# dimmer.net
KiCad netlist of a schematic drawn in EAGLE
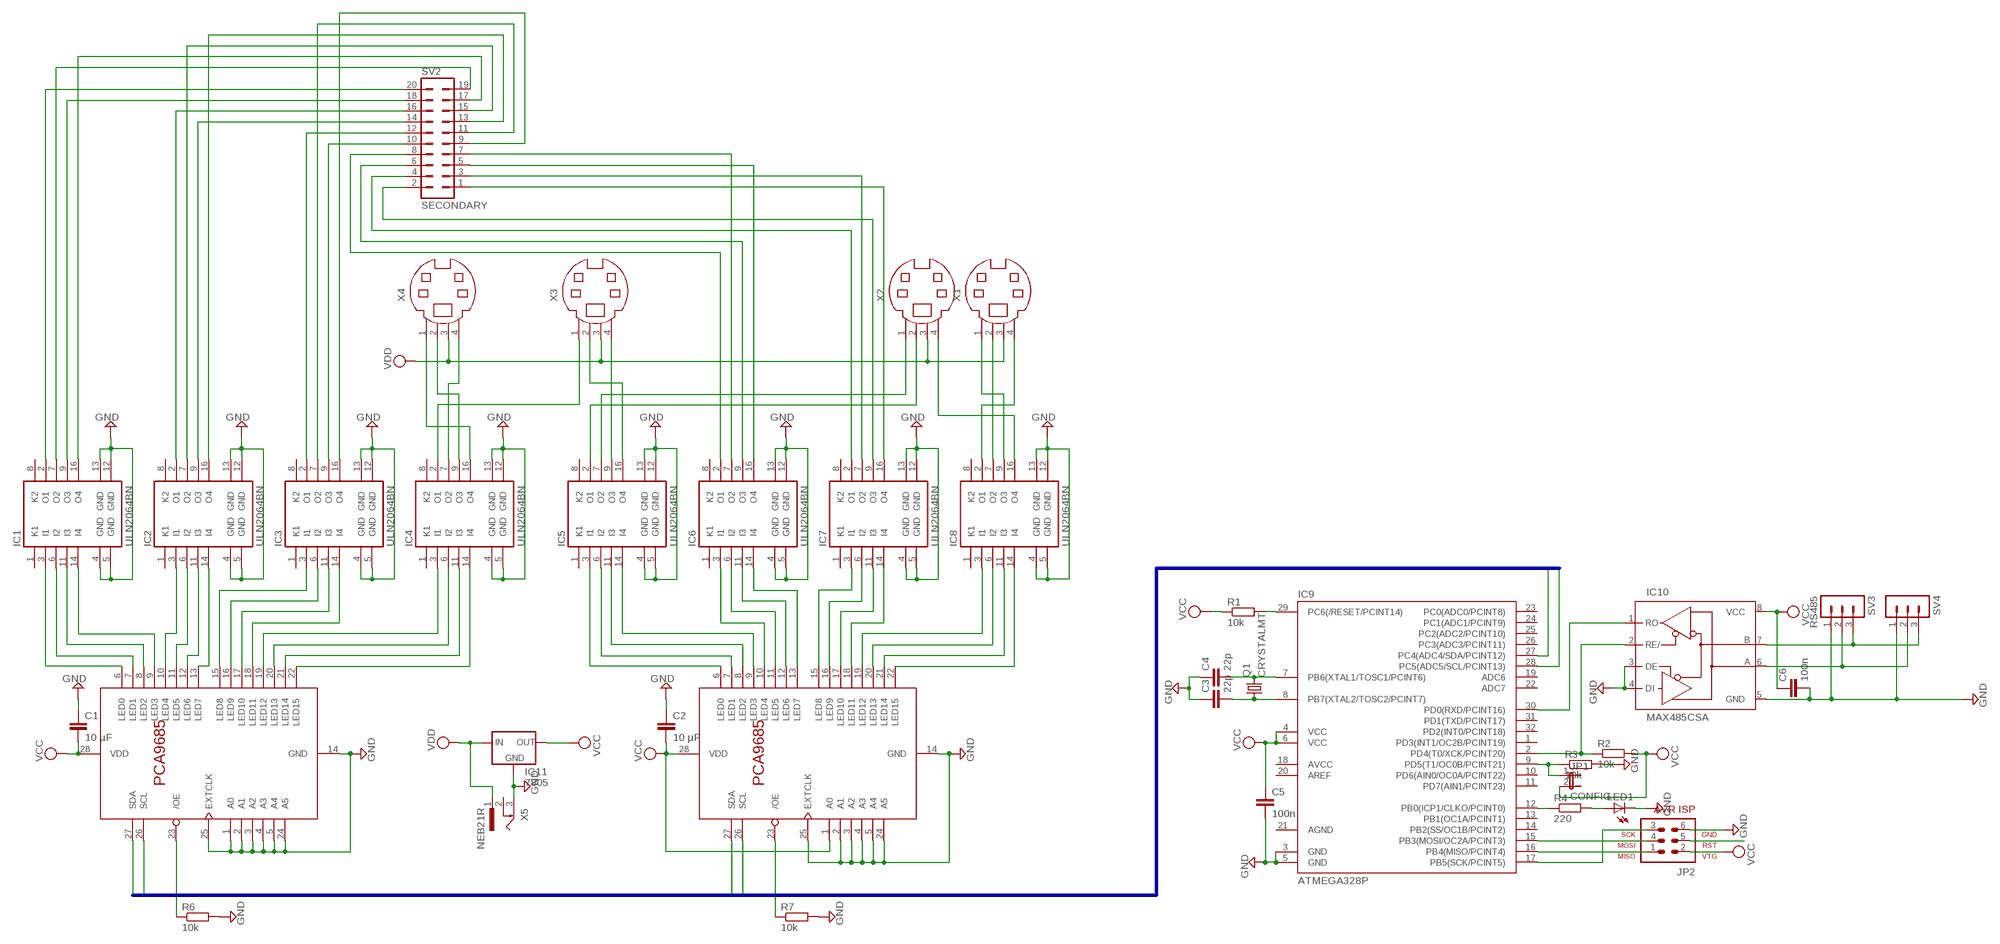
[diagram p0: schematic, sheet 1]

(export (version "E")
  (design (tool "Eeschema 10.0.6"))
  (components
    (comp (ref "C1")
      (value "10 µF")
      (footprint "eagle-import:C0805")
      (libsource (lib "eagle-import") (part "C-EUC0805"))
    )
    (comp (ref "C2")
      (value "10 µF")
      (footprint "eagle-import:C0805")
      (libsource (lib "eagle-import") (part "C-EUC0805"))
    )
    (comp (ref "C3")
      (value "22p")
      (footprint "eagle-import:C0805")
      (libsource (lib "eagle-import") (part "C-EUC0805"))
    )
    (comp (ref "C4")
      (value "22p")
      (footprint "eagle-import:C0805")
      (libsource (lib "eagle-import") (part "C-EUC0805"))
    )
    (comp (ref "C5")
      (value "100n")
      (footprint "eagle-import:C0805")
      (libsource (lib "eagle-import") (part "C-EUC0805"))
    )
    (comp (ref "C6")
      (value "100n")
      (footprint "eagle-import:C0805")
      (libsource (lib "eagle-import") (part "C-EUC0805"))
    )
    (comp (ref "IC1")
      (value "ULN2064BN")
      (footprint "eagle-import:DIL16")
      (libsource (lib "eagle-import") (part "ULN2064BN"))
    )
    (comp (ref "IC2")
      (value "ULN2064BN")
      (footprint "eagle-import:DIL16")
      (libsource (lib "eagle-import") (part "ULN2064BN"))
    )
    (comp (ref "IC3")
      (value "ULN2064BN")
      (footprint "eagle-import:DIL16")
      (libsource (lib "eagle-import") (part "ULN2064BN"))
    )
    (comp (ref "IC4")
      (value "ULN2064BN")
      (footprint "eagle-import:DIL16")
      (libsource (lib "eagle-import") (part "ULN2064BN"))
    )
    (comp (ref "IC5")
      (value "ULN2064BN")
      (footprint "eagle-import:DIL16")
      (libsource (lib "eagle-import") (part "ULN2064BN"))
    )
    (comp (ref "IC6")
      (value "ULN2064BN")
      (footprint "eagle-import:DIL16")
      (libsource (lib "eagle-import") (part "ULN2064BN"))
    )
    (comp (ref "IC7")
      (value "ULN2064BN")
      (footprint "eagle-import:DIL16")
      (libsource (lib "eagle-import") (part "ULN2064BN"))
    )
    (comp (ref "IC8")
      (value "ULN2064BN")
      (footprint "eagle-import:DIL16")
      (libsource (lib "eagle-import") (part "ULN2064BN"))
    )
    (comp (ref "IC9")
      (value "ATMEGA328P")
      (footprint "eagle-import:TQFP32-08")
      (libsource (lib "eagle-import") (part "MEGA48/88/168-AU"))
    )
    (comp (ref "IC10")
      (value "MAX485CSA")
      (footprint "eagle-import:SO08")
      (fields (field (name "MPN") "MAX3468CSA+"))
      (libsource (lib "eagle-import") (part "MAX34SA68C"))
    )
    (comp (ref "IC11")
      (value "7805")
      (footprint "eagle-import:78XXS")
      (libsource (lib "eagle-import") (part "78XXS"))
    )
    (comp (ref "JP1")
      (value "CONFIG")
      (footprint "eagle-import:JP1")
      (libsource (lib "eagle-import") (part "JP1E"))
    )
    (comp (ref "JP2")
      (value "AVR-ISP-6")
      (footprint "eagle-import:AVR-ISP-6")
      (libsource (lib "eagle-import") (part "AVR-ISP-6"))
    )
    (comp (ref "LED1")
      (value "LEDCHIP-LED0603")
      (footprint "eagle-import:CHIP-LED0603")
      (libsource (lib "eagle-import") (part "LEDCHIP-LED0603"))
    )
    (comp (ref "Q1")
      (value "CRYSTALMT")
      (footprint "eagle-import:MT")
      (libsource (lib "eagle-import") (part "CRYSTALMT"))
    )
    (comp (ref "R1")
      (value "10k")
      (footprint "eagle-import:R0805")
      (libsource (lib "eagle-import") (part "R-EU_R0805"))
    )
    (comp (ref "R2")
      (value "10k")
      (footprint "eagle-import:R0805")
      (libsource (lib "eagle-import") (part "R-EU_R0805"))
    )
    (comp (ref "R3")
      (value "10k")
      (footprint "eagle-import:R0805")
      (libsource (lib "eagle-import") (part "R-EU_R0805"))
    )
    (comp (ref "R4")
      (value "220")
      (footprint "eagle-import:R0805")
      (libsource (lib "eagle-import") (part "R-EU_R0805"))
    )
    (comp (ref "R6")
      (value "10k")
      (footprint "eagle-import:R0805")
      (libsource (lib "eagle-import") (part "R-EU_R0805"))
    )
    (comp (ref "R7")
      (value "10k")
      (footprint "eagle-import:R0805")
      (libsource (lib "eagle-import") (part "R-EU_R0805"))
    )
    (comp (ref "SV2")
      (value "SECONDARY")
      (footprint "eagle-import:MA10-2")
      (libsource (lib "eagle-import") (part "MA10-2"))
    )
    (comp (ref "SV3")
      (value "RS485")
      (footprint "eagle-import:MA03-1")
      (libsource (lib "eagle-import") (part "MA03-1"))
    )
    (comp (ref "SV4")
      (value "MA03-1")
      (footprint "eagle-import:MA03-1")
      (libsource (lib "eagle-import") (part "MA03-1"))
    )
    (comp (ref "U$1")
      (value "PCA9685PW")
      (footprint "eagle-import:TSSOP28")
      (libsource (lib "eagle-import") (part "PCA9685PW"))
    )
    (comp (ref "U$2")
      (value "PCA9685PW")
      (footprint "eagle-import:TSSOP28")
      (libsource (lib "eagle-import") (part "PCA9685PW"))
    )
    (comp (ref "X1")
      (value "MD04S")
      (footprint "eagle-import:MDIN04S")
      (libsource (lib "eagle-import") (part "MD04S"))
    )
    (comp (ref "X2")
      (value "MD04S")
      (footprint "eagle-import:MDIN04S")
      (libsource (lib "eagle-import") (part "MD04S"))
    )
    (comp (ref "X3")
      (value "MD04S")
      (footprint "eagle-import:MDIN04S")
      (libsource (lib "eagle-import") (part "MD04S"))
    )
    (comp (ref "X4")
      (value "MD04S")
      (footprint "eagle-import:MDIN04S")
      (libsource (lib "eagle-import") (part "MD04S"))
    )
    (comp (ref "X5")
      (value "NEB21R")
      (footprint "eagle-import:NEB21R")
      (fields (field (name "MPN") "NEB 21 R"))
      (libsource (lib "eagle-import") (part "NEB21R"))
    )
  )
  (nets
    (net (code "1") (name "/AGND") (class "Default")
      (node (ref "IC9") (pin "21") (pinfunction "AGND_21") (pintype "power_in"))
    )
    (net (code "2") (name "/RESET") (class "Default")
      (node (ref "IC9") (pin "29") (pinfunction "PC6(/RESET/PCINT14)_29") (pintype "bidirectional"))
      (node (ref "JP2") (pin "5") (pinfunction "5_5") (pintype "passive"))
      (node (ref "R1") (pin "2") (pinfunction "2_2") (pintype "passive"))
    )
    (net (code "3") (name "/SCL") (class "Default")
      (node (ref "IC9") (pin "28") (pinfunction "PC5(ADC5/SCL/PCINT13)_28") (pintype "bidirectional"))
      (node (ref "U$1") (pin "26") (pinfunction "SCL_26") (pintype "bidirectional"))
      (node (ref "U$2") (pin "26") (pinfunction "SCL_26") (pintype "bidirectional"))
    )
    (net (code "4") (name "/SDA") (class "Default")
      (node (ref "IC9") (pin "27") (pinfunction "PC4(ADC4/SDA/PCINT12)_27") (pintype "bidirectional"))
      (node (ref "U$1") (pin "27") (pinfunction "SDA_27") (pintype "bidirectional"))
      (node (ref "U$2") (pin "27") (pinfunction "SDA_27") (pintype "bidirectional"))
    )
    (net (code "5") (name "GND") (class "Default")
      (node (ref "C1") (pin "1") (pinfunction "1_1") (pintype "passive"))
      (node (ref "C2") (pin "1") (pinfunction "1_1") (pintype "passive"))
      (node (ref "C3") (pin "1") (pinfunction "1_1") (pintype "passive"))
      (node (ref "C4") (pin "1") (pinfunction "1_1") (pintype "passive"))
      (node (ref "C5") (pin "2") (pinfunction "2_2") (pintype "passive"))
      (node (ref "C6") (pin "2") (pinfunction "2_2") (pintype "passive"))
      (node (ref "IC1") (pin "12") (pinfunction "GND_12") (pintype "power_in"))
      (node (ref "IC1") (pin "13") (pinfunction "GND_13") (pintype "power_in"))
      (node (ref "IC1") (pin "4") (pinfunction "GND_4") (pintype "power_in"))
      (node (ref "IC1") (pin "5") (pinfunction "GND_5") (pintype "power_in"))
      (node (ref "IC10") (pin "3") (pinfunction "DE_3") (pintype "input"))
      (node (ref "IC10") (pin "4") (pinfunction "DI_4") (pintype "input"))
      (node (ref "IC10") (pin "5") (pinfunction "GND_5") (pintype "power_in"))
      (node (ref "IC11") (pin "GND") (pinfunction "GND_GND") (pintype "input"))
      (node (ref "IC2") (pin "12") (pinfunction "GND_12") (pintype "power_in"))
      (node (ref "IC2") (pin "13") (pinfunction "GND_13") (pintype "power_in"))
      (node (ref "IC2") (pin "4") (pinfunction "GND_4") (pintype "power_in"))
      (node (ref "IC2") (pin "5") (pinfunction "GND_5") (pintype "power_in"))
      (node (ref "IC3") (pin "12") (pinfunction "GND_12") (pintype "power_in"))
      (node (ref "IC3") (pin "13") (pinfunction "GND_13") (pintype "power_in"))
      (node (ref "IC3") (pin "4") (pinfunction "GND_4") (pintype "power_in"))
      (node (ref "IC3") (pin "5") (pinfunction "GND_5") (pintype "power_in"))
      (node (ref "IC4") (pin "12") (pinfunction "GND_12") (pintype "power_in"))
      (node (ref "IC4") (pin "13") (pinfunction "GND_13") (pintype "power_in"))
      (node (ref "IC4") (pin "4") (pinfunction "GND_4") (pintype "power_in"))
      (node (ref "IC4") (pin "5") (pinfunction "GND_5") (pintype "power_in"))
      (node (ref "IC5") (pin "12") (pinfunction "GND_12") (pintype "power_in"))
      (node (ref "IC5") (pin "13") (pinfunction "GND_13") (pintype "power_in"))
      (node (ref "IC5") (pin "4") (pinfunction "GND_4") (pintype "power_in"))
      (node (ref "IC5") (pin "5") (pinfunction "GND_5") (pintype "power_in"))
      (node (ref "IC6") (pin "12") (pinfunction "GND_12") (pintype "power_in"))
      (node (ref "IC6") (pin "13") (pinfunction "GND_13") (pintype "power_in"))
      (node (ref "IC6") (pin "4") (pinfunction "GND_4") (pintype "power_in"))
      (node (ref "IC6") (pin "5") (pinfunction "GND_5") (pintype "power_in"))
      (node (ref "IC7") (pin "12") (pinfunction "GND_12") (pintype "power_in"))
      (node (ref "IC7") (pin "13") (pinfunction "GND_13") (pintype "power_in"))
      (node (ref "IC7") (pin "4") (pinfunction "GND_4") (pintype "power_in"))
      (node (ref "IC7") (pin "5") (pinfunction "GND_5") (pintype "power_in"))
      (node (ref "IC8") (pin "12") (pinfunction "GND_12") (pintype "power_in"))
      (node (ref "IC8") (pin "13") (pinfunction "GND_13") (pintype "power_in"))
      (node (ref "IC8") (pin "4") (pinfunction "GND_4") (pintype "power_in"))
      (node (ref "IC8") (pin "5") (pinfunction "GND_5") (pintype "power_in"))
      (node (ref "IC9") (pin "3") (pinfunction "GND_3") (pintype "power_in"))
      (node (ref "IC9") (pin "5") (pinfunction "GND_5") (pintype "power_in"))
      (node (ref "JP2") (pin "6") (pinfunction "6_6") (pintype "passive"))
      (node (ref "LED1") (pin "C") (pinfunction "C_C") (pintype "passive"))
      (node (ref "R3") (pin "2") (pinfunction "2_2") (pintype "passive"))
      (node (ref "R6") (pin "2") (pinfunction "2_2") (pintype "passive"))
      (node (ref "R7") (pin "2") (pinfunction "2_2") (pintype "passive"))
      (node (ref "SV3") (pin "1") (pinfunction "1_1") (pintype "passive"))
      (node (ref "SV4") (pin "1") (pinfunction "1_1") (pintype "passive"))
      (node (ref "U$1") (pin "1") (pinfunction "A0_1") (pintype "bidirectional"))
      (node (ref "U$1") (pin "14") (pinfunction "GND_14") (pintype "power_in"))
      (node (ref "U$1") (pin "2") (pinfunction "A1_2") (pintype "bidirectional"))
      (node (ref "U$1") (pin "24") (pinfunction "A5_24") (pintype "bidirectional"))
      (node (ref "U$1") (pin "25") (pinfunction "EXTCLK_25") (pintype "input"))
      (node (ref "U$1") (pin "3") (pinfunction "A2_3") (pintype "bidirectional"))
      (node (ref "U$1") (pin "4") (pinfunction "A3_4") (pintype "bidirectional"))
      (node (ref "U$1") (pin "5") (pinfunction "A4_5") (pintype "bidirectional"))
      (node (ref "U$2") (pin "14") (pinfunction "GND_14") (pintype "power_in"))
      (node (ref "U$2") (pin "2") (pinfunction "A1_2") (pintype "bidirectional"))
      (node (ref "U$2") (pin "24") (pinfunction "A5_24") (pintype "bidirectional"))
      (node (ref "U$2") (pin "25") (pinfunction "EXTCLK_25") (pintype "input"))
      (node (ref "U$2") (pin "3") (pinfunction "A2_3") (pintype "bidirectional"))
      (node (ref "U$2") (pin "4") (pinfunction "A3_4") (pintype "bidirectional"))
      (node (ref "U$2") (pin "5") (pinfunction "A4_5") (pintype "bidirectional"))
      (node (ref "X5") (pin "3") (pinfunction "3_3") (pintype "passive"))
    )
    (net (code "6") (name "Net-(IC1-I1)") (class "Default")
      (node (ref "IC1") (pin "3") (pinfunction "I1_3") (pintype "input"))
      (node (ref "U$1") (pin "6") (pinfunction "LED0_6") (pintype "bidirectional"))
    )
    (net (code "7") (name "Net-(IC1-I2)") (class "Default")
      (node (ref "IC1") (pin "6") (pinfunction "I2_6") (pintype "input"))
      (node (ref "U$1") (pin "7") (pinfunction "LED1_7") (pintype "bidirectional"))
    )
    (net (code "8") (name "Net-(IC1-I3)") (class "Default")
      (node (ref "IC1") (pin "11") (pinfunction "I3_11") (pintype "input"))
      (node (ref "U$1") (pin "8") (pinfunction "LED2_8") (pintype "bidirectional"))
    )
    (net (code "9") (name "Net-(IC1-I4)") (class "Default")
      (node (ref "IC1") (pin "14") (pinfunction "I4_14") (pintype "input"))
      (node (ref "U$1") (pin "9") (pinfunction "LED3_9") (pintype "bidirectional"))
    )
    (net (code "10") (name "Net-(IC1-O1)") (class "Default")
      (node (ref "IC1") (pin "2") (pinfunction "O1_2") (pintype "open_collector"))
      (node (ref "SV2") (pin "20") (pinfunction "20_20") (pintype "passive"))
    )
    (net (code "11") (name "Net-(IC1-O2)") (class "Default")
      (node (ref "IC1") (pin "7") (pinfunction "O2_7") (pintype "open_collector"))
      (node (ref "SV2") (pin "19") (pinfunction "19_19") (pintype "passive"))
    )
    (net (code "12") (name "Net-(IC1-O3)") (class "Default")
      (node (ref "IC1") (pin "9") (pinfunction "O3_9") (pintype "open_collector"))
      (node (ref "SV2") (pin "18") (pinfunction "18_18") (pintype "passive"))
    )
    (net (code "13") (name "Net-(IC1-O4)") (class "Default")
      (node (ref "IC1") (pin "16") (pinfunction "O4_16") (pintype "open_collector"))
      (node (ref "SV2") (pin "17") (pinfunction "17_17") (pintype "passive"))
    )
    (net (code "14") (name "Net-(IC2-I1)") (class "Default")
      (node (ref "IC2") (pin "3") (pinfunction "I1_3") (pintype "input"))
      (node (ref "U$1") (pin "10") (pinfunction "LED4_10") (pintype "bidirectional"))
    )
    (net (code "15") (name "Net-(IC2-I2)") (class "Default")
      (node (ref "IC2") (pin "6") (pinfunction "I2_6") (pintype "input"))
      (node (ref "U$1") (pin "11") (pinfunction "LED5_11") (pintype "bidirectional"))
    )
    (net (code "16") (name "Net-(IC2-I3)") (class "Default")
      (node (ref "IC2") (pin "11") (pinfunction "I3_11") (pintype "input"))
      (node (ref "U$1") (pin "12") (pinfunction "LED6_12") (pintype "bidirectional"))
    )
    (net (code "17") (name "Net-(IC2-I4)") (class "Default")
      (node (ref "IC2") (pin "14") (pinfunction "I4_14") (pintype "input"))
      (node (ref "U$1") (pin "13") (pinfunction "LED7_13") (pintype "bidirectional"))
    )
    (net (code "18") (name "Net-(IC2-O1)") (class "Default")
      (node (ref "IC2") (pin "2") (pinfunction "O1_2") (pintype "open_collector"))
      (node (ref "SV2") (pin "16") (pinfunction "16_16") (pintype "passive"))
    )
    (net (code "19") (name "Net-(IC2-O2)") (class "Default")
      (node (ref "IC2") (pin "7") (pinfunction "O2_7") (pintype "open_collector"))
      (node (ref "SV2") (pin "15") (pinfunction "15_15") (pintype "passive"))
    )
    (net (code "20") (name "Net-(IC2-O3)") (class "Default")
      (node (ref "IC2") (pin "9") (pinfunction "O3_9") (pintype "open_collector"))
      (node (ref "SV2") (pin "14") (pinfunction "14_14") (pintype "passive"))
    )
    (net (code "21") (name "Net-(IC2-O4)") (class "Default")
      (node (ref "IC2") (pin "16") (pinfunction "O4_16") (pintype "open_collector"))
      (node (ref "SV2") (pin "13") (pinfunction "13_13") (pintype "passive"))
    )
    (net (code "22") (name "Net-(IC3-I1)") (class "Default")
      (node (ref "IC3") (pin "3") (pinfunction "I1_3") (pintype "input"))
      (node (ref "U$1") (pin "15") (pinfunction "LED8_15") (pintype "bidirectional"))
    )
    (net (code "23") (name "Net-(IC3-I2)") (class "Default")
      (node (ref "IC3") (pin "6") (pinfunction "I2_6") (pintype "input"))
      (node (ref "U$1") (pin "16") (pinfunction "LED9_16") (pintype "bidirectional"))
    )
    (net (code "24") (name "Net-(IC3-I3)") (class "Default")
      (node (ref "IC3") (pin "11") (pinfunction "I3_11") (pintype "input"))
      (node (ref "U$1") (pin "17") (pinfunction "LED10_17") (pintype "bidirectional"))
    )
    (net (code "25") (name "Net-(IC3-I4)") (class "Default")
      (node (ref "IC3") (pin "14") (pinfunction "I4_14") (pintype "input"))
      (node (ref "U$1") (pin "18") (pinfunction "LED11_18") (pintype "bidirectional"))
    )
    (net (code "26") (name "Net-(IC3-O1)") (class "Default")
      (node (ref "IC3") (pin "2") (pinfunction "O1_2") (pintype "open_collector"))
      (node (ref "SV2") (pin "12") (pinfunction "12_12") (pintype "passive"))
    )
    (net (code "27") (name "Net-(IC3-O2)") (class "Default")
      (node (ref "IC3") (pin "7") (pinfunction "O2_7") (pintype "open_collector"))
      (node (ref "SV2") (pin "11") (pinfunction "11_11") (pintype "passive"))
    )
    (net (code "28") (name "Net-(IC3-O3)") (class "Default")
      (node (ref "IC3") (pin "9") (pinfunction "O3_9") (pintype "open_collector"))
      (node (ref "SV2") (pin "10") (pinfunction "10_10") (pintype "passive"))
    )
    (net (code "29") (name "Net-(IC3-O4)") (class "Default")
      (node (ref "IC3") (pin "16") (pinfunction "O4_16") (pintype "open_collector"))
      (node (ref "SV2") (pin "9") (pinfunction "9_9") (pintype "passive"))
    )
    (net (code "30") (name "Net-(IC4-I1)") (class "Default")
      (node (ref "IC4") (pin "3") (pinfunction "I1_3") (pintype "input"))
      (node (ref "U$1") (pin "19") (pinfunction "LED12_19") (pintype "bidirectional"))
    )
    (net (code "31") (name "Net-(IC4-I2)") (class "Default")
      (node (ref "IC4") (pin "6") (pinfunction "I2_6") (pintype "input"))
      (node (ref "U$1") (pin "20") (pinfunction "LED13_20") (pintype "bidirectional"))
    )
    (net (code "32") (name "Net-(IC4-I3)") (class "Default")
      (node (ref "IC4") (pin "11") (pinfunction "I3_11") (pintype "input"))
      (node (ref "U$1") (pin "21") (pinfunction "LED14_21") (pintype "bidirectional"))
    )
    (net (code "33") (name "Net-(IC4-I4)") (class "Default")
      (node (ref "IC4") (pin "14") (pinfunction "I4_14") (pintype "input"))
      (node (ref "U$1") (pin "22") (pinfunction "LED15_22") (pintype "bidirectional"))
    )
    (net (code "34") (name "Net-(IC4-O1)") (class "Default")
      (node (ref "IC4") (pin "2") (pinfunction "O1_2") (pintype "open_collector"))
      (node (ref "X3") (pin "1") (pinfunction "1_1") (pintype "passive"))
    )
    (net (code "35") (name "Net-(IC4-O2)") (class "Default")
      (node (ref "IC4") (pin "7") (pinfunction "O2_7") (pintype "open_collector"))
      (node (ref "X4") (pin "4") (pinfunction "4_4") (pintype "passive"))
    )
    (net (code "36") (name "Net-(IC4-O3)") (class "Default")
      (node (ref "IC4") (pin "9") (pinfunction "O3_9") (pintype "open_collector"))
      (node (ref "X4") (pin "2") (pinfunction "2_2") (pintype "passive"))
    )
    (net (code "37") (name "Net-(IC4-O4)") (class "Default")
      (node (ref "IC4") (pin "16") (pinfunction "O4_16") (pintype "open_collector"))
      (node (ref "X4") (pin "1") (pinfunction "1_1") (pintype "passive"))
    )
    (net (code "38") (name "Net-(IC5-I1)") (class "Default")
      (node (ref "IC5") (pin "3") (pinfunction "I1_3") (pintype "input"))
      (node (ref "U$2") (pin "6") (pinfunction "LED0_6") (pintype "bidirectional"))
    )
    (net (code "39") (name "Net-(IC5-I2)") (class "Default")
      (node (ref "IC5") (pin "6") (pinfunction "I2_6") (pintype "input"))
      (node (ref "U$2") (pin "7") (pinfunction "LED1_7") (pintype "bidirectional"))
    )
    (net (code "40") (name "Net-(IC5-I3)") (class "Default")
      (node (ref "IC5") (pin "11") (pinfunction "I3_11") (pintype "input"))
      (node (ref "U$2") (pin "8") (pinfunction "LED2_8") (pintype "bidirectional"))
    )
    (net (code "41") (name "Net-(IC5-I4)") (class "Default")
      (node (ref "IC5") (pin "14") (pinfunction "I4_14") (pintype "input"))
      (node (ref "U$2") (pin "9") (pinfunction "LED3_9") (pintype "bidirectional"))
    )
    (net (code "42") (name "Net-(IC5-O1)") (class "Default")
      (node (ref "IC5") (pin "2") (pinfunction "O1_2") (pintype "open_collector"))
      (node (ref "X2") (pin "2") (pinfunction "2_2") (pintype "passive"))
    )
    (net (code "43") (name "Net-(IC5-O2)") (class "Default")
      (node (ref "IC5") (pin "7") (pinfunction "O2_7") (pintype "open_collector"))
      (node (ref "X2") (pin "1") (pinfunction "1_1") (pintype "passive"))
    )
    (net (code "44") (name "Net-(IC5-O3)") (class "Default")
      (node (ref "IC5") (pin "9") (pinfunction "O3_9") (pintype "open_collector"))
      (node (ref "X3") (pin "4") (pinfunction "4_4") (pintype "passive"))
    )
    (net (code "45") (name "Net-(IC5-O4)") (class "Default")
      (node (ref "IC5") (pin "16") (pinfunction "O4_16") (pintype "open_collector"))
      (node (ref "X3") (pin "2") (pinfunction "2_2") (pintype "passive"))
    )
    (net (code "46") (name "Net-(IC6-I1)") (class "Default")
      (node (ref "IC6") (pin "3") (pinfunction "I1_3") (pintype "input"))
      (node (ref "U$2") (pin "10") (pinfunction "LED4_10") (pintype "bidirectional"))
    )
    (net (code "47") (name "Net-(IC6-I2)") (class "Default")
      (node (ref "IC6") (pin "6") (pinfunction "I2_6") (pintype "input"))
      (node (ref "U$2") (pin "11") (pinfunction "LED5_11") (pintype "bidirectional"))
    )
    (net (code "48") (name "Net-(IC6-I3)") (class "Default")
      (node (ref "IC6") (pin "11") (pinfunction "I3_11") (pintype "input"))
      (node (ref "U$2") (pin "12") (pinfunction "LED6_12") (pintype "bidirectional"))
    )
    (net (code "49") (name "Net-(IC6-I4)") (class "Default")
      (node (ref "IC6") (pin "14") (pinfunction "I4_14") (pintype "input"))
      (node (ref "U$2") (pin "13") (pinfunction "LED7_13") (pintype "bidirectional"))
    )
    (net (code "50") (name "Net-(IC6-O1)") (class "Default")
      (node (ref "IC6") (pin "2") (pinfunction "O1_2") (pintype "open_collector"))
      (node (ref "SV2") (pin "8") (pinfunction "8_8") (pintype "passive"))
    )
    (net (code "51") (name "Net-(IC6-O2)") (class "Default")
      (node (ref "IC6") (pin "7") (pinfunction "O2_7") (pintype "open_collector"))
      (node (ref "SV2") (pin "7") (pinfunction "7_7") (pintype "passive"))
    )
    (net (code "52") (name "Net-(IC6-O3)") (class "Default")
      (node (ref "IC6") (pin "9") (pinfunction "O3_9") (pintype "open_collector"))
      (node (ref "SV2") (pin "6") (pinfunction "6_6") (pintype "passive"))
    )
    (net (code "53") (name "Net-(IC6-O4)") (class "Default")
      (node (ref "IC6") (pin "16") (pinfunction "O4_16") (pintype "open_collector"))
      (node (ref "SV2") (pin "5") (pinfunction "5_5") (pintype "passive"))
    )
    (net (code "54") (name "Net-(IC7-I1)") (class "Default")
      (node (ref "IC7") (pin "3") (pinfunction "I1_3") (pintype "input"))
      (node (ref "U$2") (pin "15") (pinfunction "LED8_15") (pintype "bidirectional"))
    )
    (net (code "55") (name "Net-(IC7-I2)") (class "Default")
      (node (ref "IC7") (pin "6") (pinfunction "I2_6") (pintype "input"))
      (node (ref "U$2") (pin "16") (pinfunction "LED9_16") (pintype "bidirectional"))
    )
    (net (code "56") (name "Net-(IC7-I3)") (class "Default")
      (node (ref "IC7") (pin "11") (pinfunction "I3_11") (pintype "input"))
      (node (ref "U$2") (pin "17") (pinfunction "LED10_17") (pintype "bidirectional"))
    )
    (net (code "57") (name "Net-(IC7-I4)") (class "Default")
      (node (ref "IC7") (pin "14") (pinfunction "I4_14") (pintype "input"))
      (node (ref "U$2") (pin "18") (pinfunction "LED11_18") (pintype "bidirectional"))
    )
    (net (code "58") (name "Net-(IC7-O1)") (class "Default")
      (node (ref "IC7") (pin "2") (pinfunction "O1_2") (pintype "open_collector"))
      (node (ref "SV2") (pin "4") (pinfunction "4_4") (pintype "passive"))
    )
    (net (code "59") (name "Net-(IC7-O2)") (class "Default")
      (node (ref "IC7") (pin "7") (pinfunction "O2_7") (pintype "open_collector"))
      (node (ref "SV2") (pin "3") (pinfunction "3_3") (pintype "passive"))
    )
    (net (code "60") (name "Net-(IC7-O3)") (class "Default")
      (node (ref "IC7") (pin "9") (pinfunction "O3_9") (pintype "open_collector"))
      (node (ref "SV2") (pin "2") (pinfunction "2_2") (pintype "passive"))
    )
    (net (code "61") (name "Net-(IC7-O4)") (class "Default")
      (node (ref "IC7") (pin "16") (pinfunction "O4_16") (pintype "open_collector"))
      (node (ref "SV2") (pin "1") (pinfunction "1_1") (pintype "passive"))
    )
    (net (code "62") (name "Net-(IC8-I1)") (class "Default")
      (node (ref "IC8") (pin "3") (pinfunction "I1_3") (pintype "input"))
      (node (ref "U$2") (pin "19") (pinfunction "LED12_19") (pintype "bidirectional"))
    )
    (net (code "63") (name "Net-(IC8-I2)") (class "Default")
      (node (ref "IC8") (pin "6") (pinfunction "I2_6") (pintype "input"))
      (node (ref "U$2") (pin "20") (pinfunction "LED13_20") (pintype "bidirectional"))
    )
    (net (code "64") (name "Net-(IC8-I3)") (class "Default")
      (node (ref "IC8") (pin "11") (pinfunction "I3_11") (pintype "input"))
      (node (ref "U$2") (pin "21") (pinfunction "LED14_21") (pintype "bidirectional"))
    )
    (net (code "65") (name "Net-(IC8-I4)") (class "Default")
      (node (ref "IC8") (pin "14") (pinfunction "I4_14") (pintype "input"))
      (node (ref "U$2") (pin "22") (pinfunction "LED15_22") (pintype "bidirectional"))
    )
    (net (code "66") (name "Net-(IC8-O1)") (class "Default")
      (node (ref "IC8") (pin "2") (pinfunction "O1_2") (pintype "open_collector"))
      (node (ref "X1") (pin "4") (pinfunction "4_4") (pintype "passive"))
    )
    (net (code "67") (name "Net-(IC8-O2)") (class "Default")
      (node (ref "IC8") (pin "7") (pinfunction "O2_7") (pintype "open_collector"))
      (node (ref "X1") (pin "2") (pinfunction "2_2") (pintype "passive"))
    )
    (net (code "68") (name "Net-(IC8-O3)") (class "Default")
      (node (ref "IC8") (pin "9") (pinfunction "O3_9") (pintype "open_collector"))
      (node (ref "X1") (pin "1") (pinfunction "1_1") (pintype "passive"))
    )
    (net (code "69") (name "Net-(IC8-O4)") (class "Default")
      (node (ref "IC8") (pin "16") (pinfunction "O4_16") (pintype "open_collector"))
      (node (ref "X2") (pin "4") (pinfunction "4_4") (pintype "passive"))
    )
    (net (code "70") (name "Net-(IC9-PB0(ICP1{slash}CLKO{slash}PCINT0))") (class "Default")
      (node (ref "IC9") (pin "12") (pinfunction "PB0(ICP1/CLKO/PCINT0)_12") (pintype "bidirectional"))
      (node (ref "R4") (pin "1") (pinfunction "1_1") (pintype "passive"))
    )
    (net (code "71") (name "Net-(IC9-PB3(MOSI{slash}OC2A{slash}PCINT3))") (class "Default")
      (node (ref "IC9") (pin "15") (pinfunction "PB3(MOSI/OC2A/PCINT3)_15") (pintype "bidirectional"))
      (node (ref "JP2") (pin "4") (pinfunction "4_4") (pintype "passive"))
    )
    (net (code "72") (name "Net-(IC9-PB4(MISO{slash}PCINT4))") (class "Default")
      (node (ref "IC9") (pin "16") (pinfunction "PB4(MISO/PCINT4)_16") (pintype "bidirectional"))
      (node (ref "JP2") (pin "1") (pinfunction "1_1") (pintype "passive"))
    )
    (net (code "73") (name "Net-(IC9-PB5(SCK{slash}PCINT5))") (class "Default")
      (node (ref "IC9") (pin "17") (pinfunction "PB5(SCK/PCINT5)_17") (pintype "bidirectional"))
      (node (ref "JP2") (pin "3") (pinfunction "3_3") (pintype "passive"))
    )
    (net (code "74") (name "Net-(IC9-PB6(XTAL1{slash}TOSC1{slash}PCINT6))") (class "Default")
      (node (ref "C4") (pin "2") (pinfunction "2_2") (pintype "passive"))
      (node (ref "IC9") (pin "7") (pinfunction "PB6(XTAL1/TOSC1/PCINT6)_7") (pintype "bidirectional"))
      (node (ref "Q1") (pin "P3") (pinfunction "2_P3") (pintype "passive"))
    )
    (net (code "75") (name "Net-(IC9-PB7(XTAL2{slash}TOSC2{slash}PCINT7))") (class "Default")
      (node (ref "C3") (pin "2") (pinfunction "2_2") (pintype "passive"))
      (node (ref "IC9") (pin "8") (pinfunction "PB7(XTAL2/TOSC2/PCINT7)_8") (pintype "bidirectional"))
      (node (ref "Q1") (pin "P1") (pinfunction "1_P1") (pintype "passive"))
    )
    (net (code "76") (name "Net-(IC9-PD5(T1{slash}OC0B{slash}PCINT21))") (class "Default")
      (node (ref "IC9") (pin "9") (pinfunction "PD5(T1/OC0B/PCINT21)_9") (pintype "bidirectional"))
      (node (ref "JP1") (pin "1") (pinfunction "1_1") (pintype "passive"))
      (node (ref "R3") (pin "1") (pinfunction "1_1") (pintype "passive"))
    )
    (net (code "77") (name "Net-(IC10-A)") (class "Default")
      (node (ref "IC10") (pin "6") (pinfunction "A_6") (pintype "passive"))
      (node (ref "SV3") (pin "2") (pinfunction "2_2") (pintype "passive"))
      (node (ref "SV4") (pin "2") (pinfunction "2_2") (pintype "passive"))
    )
    (net (code "78") (name "Net-(IC10-B)") (class "Default")
      (node (ref "IC10") (pin "7") (pinfunction "B_7") (pintype "passive"))
      (node (ref "SV3") (pin "3") (pinfunction "3_3") (pintype "passive"))
      (node (ref "SV4") (pin "3") (pinfunction "3_3") (pintype "passive"))
    )
    (net (code "79") (name "Net-(IC10-RE{slash})") (class "Default")
      (node (ref "IC10") (pin "2") (pinfunction "RE/_2") (pintype "input"))
      (node (ref "IC9") (pin "2") (pinfunction "PD4(T0/XCK/PCINT20)_2") (pintype "bidirectional"))
      (node (ref "R2") (pin "1") (pinfunction "1_1") (pintype "passive"))
    )
    (net (code "80") (name "Net-(IC10-RO)") (class "Default")
      (node (ref "IC10") (pin "1") (pinfunction "RO_1") (pintype "output"))
      (node (ref "IC9") (pin "30") (pinfunction "PD0(RXD/PCINT16)_30") (pintype "bidirectional"))
    )
    (net (code "81") (name "Net-(LED1-PadA)") (class "Default")
      (node (ref "LED1") (pin "A") (pinfunction "A_A") (pintype "passive"))
      (node (ref "R4") (pin "2") (pinfunction "2_2") (pintype "passive"))
    )
    (net (code "82") (name "Net-(U$1-{slash}OE)") (class "Default")
      (node (ref "R6") (pin "1") (pinfunction "1_1") (pintype "passive"))
      (node (ref "U$1") (pin "23") (pinfunction "/OE_23") (pintype "bidirectional"))
    )
    (net (code "83") (name "Net-(U$2-{slash}OE)") (class "Default")
      (node (ref "R7") (pin "1") (pinfunction "1_1") (pintype "passive"))
      (node (ref "U$2") (pin "23") (pinfunction "/OE_23") (pintype "bidirectional"))
    )
    (net (code "84") (name "VCC") (class "Default")
      (node (ref "C1") (pin "2") (pinfunction "2_2") (pintype "passive"))
      (node (ref "C2") (pin "2") (pinfunction "2_2") (pintype "passive"))
      (node (ref "C5") (pin "1") (pinfunction "1_1") (pintype "passive"))
      (node (ref "C6") (pin "1") (pinfunction "1_1") (pintype "passive"))
      (node (ref "IC10") (pin "8") (pinfunction "VCC_8") (pintype "power_in"))
      (node (ref "IC11") (pin "OUT") (pinfunction "OUT_OUT") (pintype "passive"))
      (node (ref "IC9") (pin "4") (pinfunction "VCC_4") (pintype "power_in"))
      (node (ref "IC9") (pin "6") (pinfunction "VCC_6") (pintype "power_in"))
      (node (ref "JP1") (pin "2") (pinfunction "2_2") (pintype "passive"))
      (node (ref "JP2") (pin "2") (pinfunction "2_2") (pintype "passive"))
      (node (ref "R1") (pin "1") (pinfunction "1_1") (pintype "passive"))
      (node (ref "R2") (pin "2") (pinfunction "2_2") (pintype "passive"))
      (node (ref "U$1") (pin "28") (pinfunction "VDD_28") (pintype "power_in"))
      (node (ref "U$2") (pin "1") (pinfunction "A0_1") (pintype "bidirectional"))
      (node (ref "U$2") (pin "28") (pinfunction "VDD_28") (pintype "power_in"))
    )
    (net (code "85") (name "VDD") (class "Default")
      (node (ref "IC11") (pin "IN") (pinfunction "IN_IN") (pintype "input"))
      (node (ref "X1") (pin "3") (pinfunction "3_3") (pintype "passive"))
      (node (ref "X2") (pin "3") (pinfunction "3_3") (pintype "passive"))
      (node (ref "X3") (pin "3") (pinfunction "3_3") (pintype "passive"))
      (node (ref "X4") (pin "3") (pinfunction "3_3") (pintype "passive"))
      (node (ref "X5") (pin "1") (pinfunction "1_1") (pintype "passive"))
    )
    (net (code "86") (name "unconnected-(IC1-K1-Pad1)") (class "Default")
      (node (ref "IC1") (pin "1") (pinfunction "K1_1") (pintype "passive"))
    )
    (net (code "87") (name "unconnected-(IC1-K2-Pad8)") (class "Default")
      (node (ref "IC1") (pin "8") (pinfunction "K2_8") (pintype "passive"))
    )
    (net (code "88") (name "unconnected-(IC2-K1-Pad1)") (class "Default")
      (node (ref "IC2") (pin "1") (pinfunction "K1_1") (pintype "passive"))
    )
    (net (code "89") (name "unconnected-(IC2-K2-Pad8)") (class "Default")
      (node (ref "IC2") (pin "8") (pinfunction "K2_8") (pintype "passive"))
    )
    (net (code "90") (name "unconnected-(IC3-K1-Pad1)") (class "Default")
      (node (ref "IC3") (pin "1") (pinfunction "K1_1") (pintype "passive"))
    )
    (net (code "91") (name "unconnected-(IC3-K2-Pad8)") (class "Default")
      (node (ref "IC3") (pin "8") (pinfunction "K2_8") (pintype "passive"))
    )
    (net (code "92") (name "unconnected-(IC4-K1-Pad1)") (class "Default")
      (node (ref "IC4") (pin "1") (pinfunction "K1_1") (pintype "passive"))
    )
    (net (code "93") (name "unconnected-(IC4-K2-Pad8)") (class "Default")
      (node (ref "IC4") (pin "8") (pinfunction "K2_8") (pintype "passive"))
    )
    (net (code "94") (name "unconnected-(IC5-K1-Pad1)") (class "Default")
      (node (ref "IC5") (pin "1") (pinfunction "K1_1") (pintype "passive"))
    )
    (net (code "95") (name "unconnected-(IC5-K2-Pad8)") (class "Default")
      (node (ref "IC5") (pin "8") (pinfunction "K2_8") (pintype "passive"))
    )
    (net (code "96") (name "unconnected-(IC6-K1-Pad1)") (class "Default")
      (node (ref "IC6") (pin "1") (pinfunction "K1_1") (pintype "passive"))
    )
    (net (code "97") (name "unconnected-(IC6-K2-Pad8)") (class "Default")
      (node (ref "IC6") (pin "8") (pinfunction "K2_8") (pintype "passive"))
    )
    (net (code "98") (name "unconnected-(IC7-K1-Pad1)") (class "Default")
      (node (ref "IC7") (pin "1") (pinfunction "K1_1") (pintype "passive"))
    )
    (net (code "99") (name "unconnected-(IC7-K2-Pad8)") (class "Default")
      (node (ref "IC7") (pin "8") (pinfunction "K2_8") (pintype "passive"))
    )
    (net (code "100") (name "unconnected-(IC8-K1-Pad1)") (class "Default")
      (node (ref "IC8") (pin "1") (pinfunction "K1_1") (pintype "passive"))
    )
    (net (code "101") (name "unconnected-(IC8-K2-Pad8)") (class "Default")
      (node (ref "IC8") (pin "8") (pinfunction "K2_8") (pintype "passive"))
    )
    (net (code "102") (name "unconnected-(IC9-ADC6-Pad19)") (class "Default")
      (node (ref "IC9") (pin "19") (pinfunction "ADC6_19") (pintype "passive"))
    )
    (net (code "103") (name "unconnected-(IC9-ADC7-Pad22)") (class "Default")
      (node (ref "IC9") (pin "22") (pinfunction "ADC7_22") (pintype "passive"))
    )
    (net (code "104") (name "unconnected-(IC9-AREF-Pad20)") (class "Default")
      (node (ref "IC9") (pin "20") (pinfunction "AREF_20") (pintype "passive"))
    )
    (net (code "105") (name "unconnected-(IC9-AVCC-Pad18)") (class "Default")
      (node (ref "IC9") (pin "18") (pinfunction "AVCC_18") (pintype "passive"))
    )
    (net (code "106") (name "unconnected-(IC9-PB1(OC1A{slash}PCINT1)-Pad13)") (class "Default")
      (node (ref "IC9") (pin "13") (pinfunction "PB1(OC1A/PCINT1)_13") (pintype "bidirectional"))
    )
    (net (code "107") (name "unconnected-(IC9-PB2(SS{slash}OC1B{slash}PCINT2)-Pad14)") (class "Default")
      (node (ref "IC9") (pin "14") (pinfunction "PB2(SS/OC1B/PCINT2)_14") (pintype "bidirectional"))
    )
    (net (code "108") (name "unconnected-(IC9-PC0(ADC0{slash}PCINT8)-Pad23)") (class "Default")
      (node (ref "IC9") (pin "23") (pinfunction "PC0(ADC0/PCINT8)_23") (pintype "bidirectional"))
    )
    (net (code "109") (name "unconnected-(IC9-PC1(ADC1{slash}PCINT9)-Pad24)") (class "Default")
      (node (ref "IC9") (pin "24") (pinfunction "PC1(ADC1/PCINT9)_24") (pintype "bidirectional"))
    )
    (net (code "110") (name "unconnected-(IC9-PC2(ADC2{slash}PCINT10)-Pad25)") (class "Default")
      (node (ref "IC9") (pin "25") (pinfunction "PC2(ADC2/PCINT10)_25") (pintype "bidirectional"))
    )
    (net (code "111") (name "unconnected-(IC9-PC3(ADC3{slash}PCINT11)-Pad26)") (class "Default")
      (node (ref "IC9") (pin "26") (pinfunction "PC3(ADC3/PCINT11)_26") (pintype "bidirectional"))
    )
    (net (code "112") (name "unconnected-(IC9-PD1(TXD{slash}PCINT17)-Pad31)") (class "Default")
      (node (ref "IC9") (pin "31") (pinfunction "PD1(TXD/PCINT17)_31") (pintype "bidirectional"))
    )
    (net (code "113") (name "unconnected-(IC9-PD2(INT0{slash}PCINT18)-Pad32)") (class "Default")
      (node (ref "IC9") (pin "32") (pinfunction "PD2(INT0/PCINT18)_32") (pintype "bidirectional"))
    )
    (net (code "114") (name "unconnected-(IC9-PD3(INT1{slash}OC2B{slash}PCINT19)-Pad1)") (class "Default")
      (node (ref "IC9") (pin "1") (pinfunction "PD3(INT1/OC2B/PCINT19)_1") (pintype "bidirectional"))
    )
    (net (code "115") (name "unconnected-(IC9-PD6(AIN0{slash}OC0A{slash}PCINT22)-Pad10)") (class "Default")
      (node (ref "IC9") (pin "10") (pinfunction "PD6(AIN0/OC0A/PCINT22)_10") (pintype "bidirectional"))
    )
    (net (code "116") (name "unconnected-(IC9-PD7(AIN1{slash}PCINT23)-Pad11)") (class "Default")
      (node (ref "IC9") (pin "11") (pinfunction "PD7(AIN1/PCINT23)_11") (pintype "bidirectional"))
    )
    (net (code "117") (name "unconnected-(X5-Pad2)") (class "Default")
      (node (ref "X5") (pin "2") (pinfunction "2_2") (pintype "passive"))
    )
  )
)
